# Main_Connector.net
KiCad netlist of a schematic drawn in Altium Designer
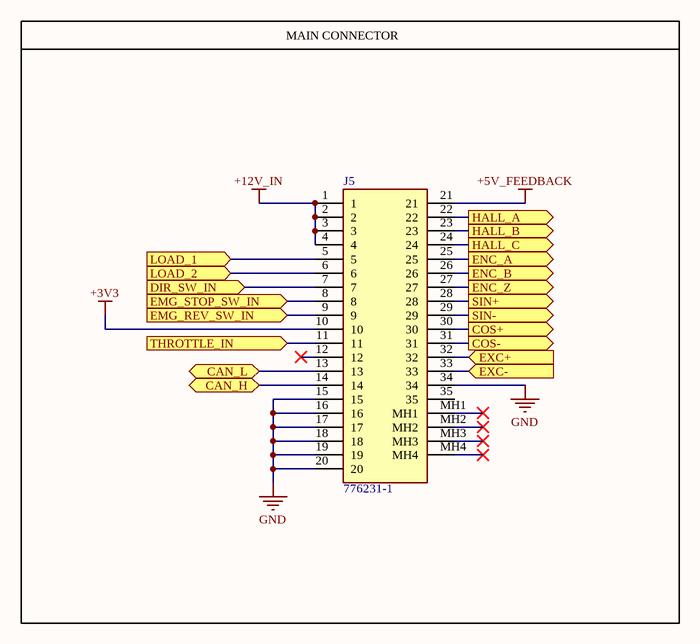
[diagram p0: Main_Connector.SchDoc]

(export (version "E")
  (design (tool "Eeschema 10.0.6"))
  (components
    (comp (ref "J5")
      (value "776231-1")
      (footprint "7762311")
      (description "Connector")
      (fields (field (name "MOUSER PART NUMBER") "571-776231-1"))
      (libsource (lib "My_Integrated_Lib") (part "776231-1"))
    )
  )
  (nets
    (net (code "1") (name "+3V3") (class "Default")
      (node (ref "J5") (pin "10") (pinfunction "10_10") (pintype "passive"))
    )
    (net (code "2") (name "+5V_FEEDBACK") (class "Default")
      (node (ref "J5") (pin "21") (pinfunction "21_21") (pintype "passive"))
    )
    (net (code "3") (name "+12V_IN") (class "Default")
      (node (ref "J5") (pin "1") (pinfunction "1_1") (pintype "passive"))
      (node (ref "J5") (pin "2") (pinfunction "2_2") (pintype "passive"))
      (node (ref "J5") (pin "3") (pinfunction "3_3") (pintype "passive"))
      (node (ref "J5") (pin "4") (pinfunction "4_4") (pintype "passive"))
    )
    (net (code "4") (name "/CAN_H") (class "Default")
      (node (ref "J5") (pin "14") (pinfunction "14_14") (pintype "passive"))
    )
    (net (code "5") (name "/CAN_L") (class "Default")
      (node (ref "J5") (pin "13") (pinfunction "13_13") (pintype "passive"))
    )
    (net (code "6") (name "/COS+") (class "Default")
      (node (ref "J5") (pin "30") (pinfunction "30_30") (pintype "passive"))
    )
    (net (code "7") (name "/COS-") (class "Default")
      (node (ref "J5") (pin "31") (pinfunction "31_31") (pintype "passive"))
    )
    (net (code "8") (name "/DIR_SW_IN") (class "Default")
      (node (ref "J5") (pin "7") (pinfunction "7_7") (pintype "passive"))
    )
    (net (code "9") (name "/EMG_REV_SW_IN") (class "Default")
      (node (ref "J5") (pin "9") (pinfunction "9_9") (pintype "passive"))
    )
    (net (code "10") (name "/EMG_STOP_SW_IN") (class "Default")
      (node (ref "J5") (pin "8") (pinfunction "8_8") (pintype "passive"))
    )
    (net (code "11") (name "/ENC_A") (class "Default")
      (node (ref "J5") (pin "25") (pinfunction "25_25") (pintype "passive"))
    )
    (net (code "12") (name "/ENC_B") (class "Default")
      (node (ref "J5") (pin "26") (pinfunction "26_26") (pintype "passive"))
    )
    (net (code "13") (name "/ENC_Z") (class "Default")
      (node (ref "J5") (pin "27") (pinfunction "27_27") (pintype "passive"))
    )
    (net (code "14") (name "/EXC+") (class "Default")
      (node (ref "J5") (pin "32") (pinfunction "32_32") (pintype "passive"))
    )
    (net (code "15") (name "/EXC-") (class "Default")
      (node (ref "J5") (pin "33") (pinfunction "33_33") (pintype "passive"))
    )
    (net (code "16") (name "/HALL_A") (class "Default")
      (node (ref "J5") (pin "22") (pinfunction "22_22") (pintype "passive"))
    )
    (net (code "17") (name "/HALL_B") (class "Default")
      (node (ref "J5") (pin "23") (pinfunction "23_23") (pintype "passive"))
    )
    (net (code "18") (name "/HALL_C") (class "Default")
      (node (ref "J5") (pin "24") (pinfunction "24_24") (pintype "passive"))
    )
    (net (code "19") (name "/LOAD_1") (class "Default")
      (node (ref "J5") (pin "5") (pinfunction "5_5") (pintype "passive"))
    )
    (net (code "20") (name "/LOAD_2") (class "Default")
      (node (ref "J5") (pin "6") (pinfunction "6_6") (pintype "passive"))
    )
    (net (code "21") (name "/SIN+") (class "Default")
      (node (ref "J5") (pin "28") (pinfunction "28_28") (pintype "passive"))
    )
    (net (code "22") (name "/SIN-") (class "Default")
      (node (ref "J5") (pin "29") (pinfunction "29_29") (pintype "passive"))
    )
    (net (code "23") (name "/THROTTLE_IN") (class "Default")
      (node (ref "J5") (pin "11") (pinfunction "11_11") (pintype "passive"))
    )
    (net (code "24") (name "GND") (class "Default")
      (node (ref "J5") (pin "15") (pinfunction "15_15") (pintype "passive"))
      (node (ref "J5") (pin "16") (pinfunction "16_16") (pintype "passive"))
      (node (ref "J5") (pin "17") (pinfunction "17_17") (pintype "passive"))
      (node (ref "J5") (pin "18") (pinfunction "18_18") (pintype "passive"))
      (node (ref "J5") (pin "19") (pinfunction "19_19") (pintype "passive"))
      (node (ref "J5") (pin "20") (pinfunction "20_20") (pintype "passive"))
      (node (ref "J5") (pin "34") (pinfunction "34_34") (pintype "passive"))
    )
    (net (code "25") (name "unconnected-(J5-Pad12)") (class "Default")
      (node (ref "J5") (pin "12") (pinfunction "12_12") (pintype "passive+no_connect"))
    )
    (net (code "26") (name "unconnected-(J5-Pad35)") (class "Default")
      (node (ref "J5") (pin "35") (pinfunction "35_35") (pintype "passive"))
    )
    (net (code "27") (name "unconnected-(J5-PadMH1)") (class "Default")
      (node (ref "J5") (pin "MH1") (pinfunction "MH1_MH1") (pintype "passive+no_connect"))
    )
    (net (code "28") (name "unconnected-(J5-PadMH2)") (class "Default")
      (node (ref "J5") (pin "MH2") (pinfunction "MH2_MH2") (pintype "passive+no_connect"))
    )
    (net (code "29") (name "unconnected-(J5-PadMH3)") (class "Default")
      (node (ref "J5") (pin "MH3") (pinfunction "MH3_MH3") (pintype "passive+no_connect"))
    )
    (net (code "30") (name "unconnected-(J5-PadMH4)") (class "Default")
      (node (ref "J5") (pin "MH4") (pinfunction "MH4_MH4") (pintype "passive+no_connect"))
    )
  )
)
